# HedleySensorRevB.net
KiCad netlist of a schematic drawn in EAGLE
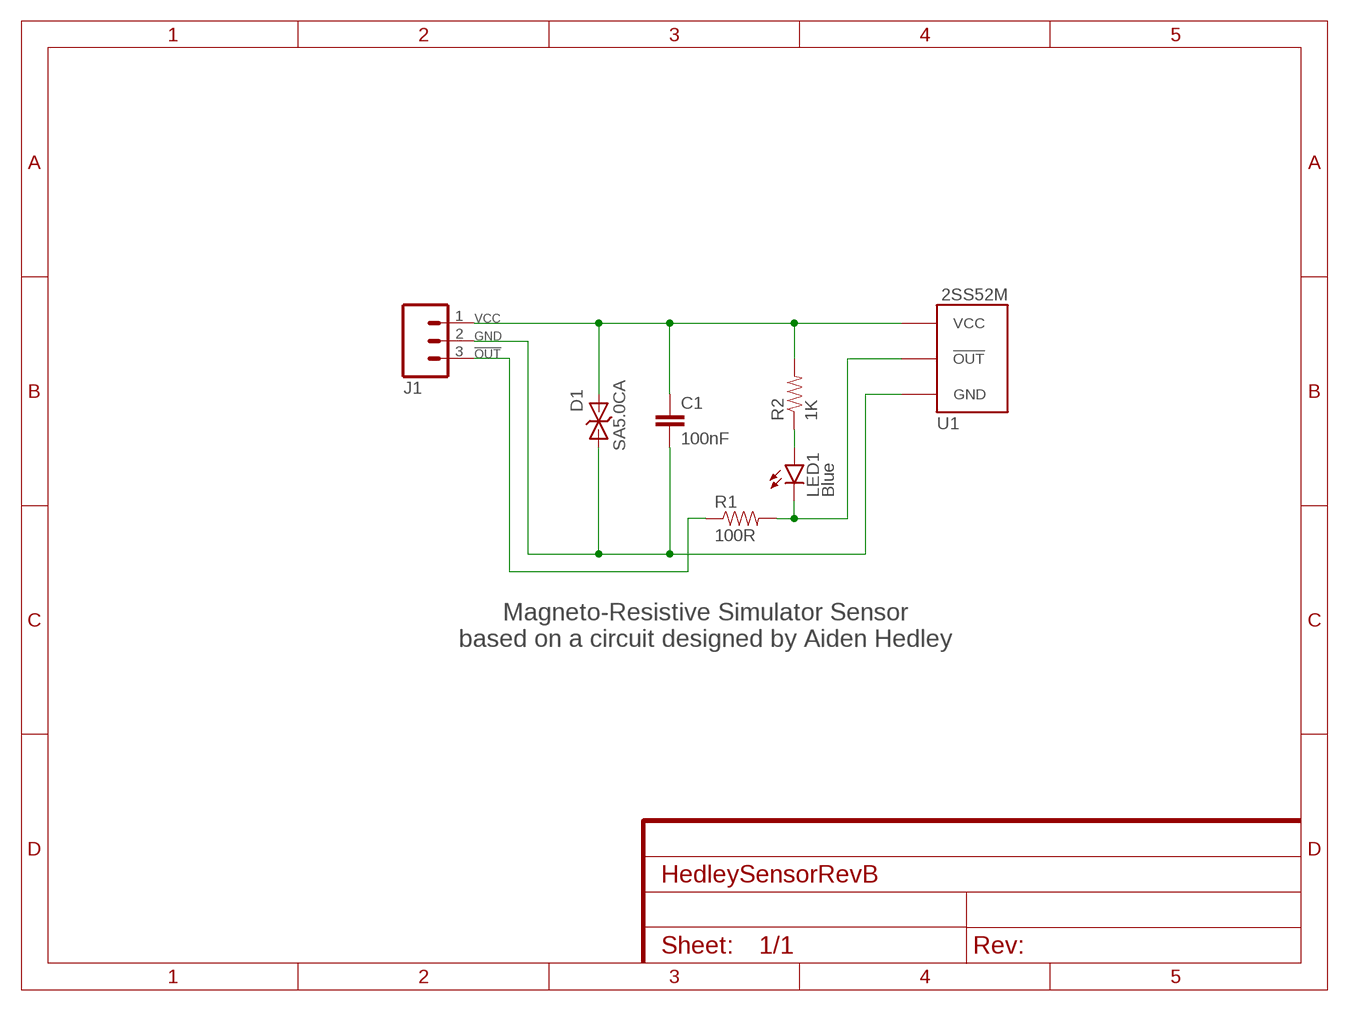
[diagram p0: schematic, sheet 1]

(export (version "E")
  (design (tool "Eeschema 10.0.6"))
  (components
    (comp (ref "C1")
      (value "100nF")
      (footprint "eagle-import:CAP-PTH-SMALL")
      (libsource (lib "eagle-import") (part "CAPPTH"))
    )
    (comp (ref "D1")
      (value "SA5.0CA")
      (footprint "eagle-import:DO41_TVS")
      (libsource (lib "eagle-import") (part "SA5.0CA"))
    )
    (comp (ref "J1")
      (value "M03PTH")
      (footprint "eagle-import:1X03")
      (libsource (lib "eagle-import") (part "M03PTH"))
    )
    (comp (ref "LED1")
      (value "Blue")
      (footprint "eagle-import:LED3MM")
      (libsource (lib "eagle-import") (part "LED3MM"))
    )
    (comp (ref "R1")
      (value "100R")
      (footprint "eagle-import:AXIAL-0.4")
      (libsource (lib "eagle-import") (part "RESISTORPTH-1/4W"))
    )
    (comp (ref "R2")
      (value "1K")
      (footprint "eagle-import:AXIAL-0.4")
      (libsource (lib "eagle-import") (part "RESISTORPTH-1/4W"))
    )
    (comp (ref "U1")
      (value "2SS52MFLAT")
      (footprint "eagle-import:2SS52M_FLAT")
      (libsource (lib "eagle-import") (part "2SS52MFLAT"))
    )
  )
  (nets
    (net (code "1") (name "/GND") (class "Default")
      (node (ref "C1") (pin "2") (pinfunction "2_2") (pintype "passive"))
      (node (ref "D1") (pin "A") (pinfunction "A_A") (pintype "passive"))
      (node (ref "J1") (pin "2") (pinfunction "2_2") (pintype "passive"))
      (node (ref "U1") (pin "P$1") (pinfunction "GND_P$1") (pintype "bidirectional"))
    )
    (net (code "2") (name "/VCC") (class "Default")
      (node (ref "C1") (pin "1") (pinfunction "1_1") (pintype "passive"))
      (node (ref "D1") (pin "C") (pinfunction "C_C") (pintype "passive"))
      (node (ref "J1") (pin "1") (pinfunction "1_1") (pintype "passive"))
      (node (ref "R2") (pin "P$2") (pinfunction "2_P$2") (pintype "passive"))
      (node (ref "U1") (pin "P$3") (pinfunction "VCC_P$3") (pintype "bidirectional"))
    )
    (net (code "3") (name "/~{OUT}") (class "Default")
      (node (ref "J1") (pin "3") (pinfunction "3_3") (pintype "passive"))
      (node (ref "R1") (pin "P$1") (pinfunction "1_P$1") (pintype "passive"))
    )
    (net (code "4") (name "Net-(LED1-C)") (class "Default")
      (node (ref "LED1") (pin "K") (pinfunction "C_K") (pintype "passive"))
      (node (ref "R1") (pin "P$2") (pinfunction "2_P$2") (pintype "passive"))
      (node (ref "U1") (pin "P$2") (pinfunction "~{OUT}_P$2") (pintype "bidirectional"))
    )
    (net (code "5") (name "Net-(R2-1)") (class "Default")
      (node (ref "LED1") (pin "A") (pinfunction "A_A") (pintype "passive"))
      (node (ref "R2") (pin "P$1") (pinfunction "1_P$1") (pintype "passive"))
    )
  )
)
